# xen_teensy_controls_template.net
KiCad netlist of a schematic drawn in EAGLE
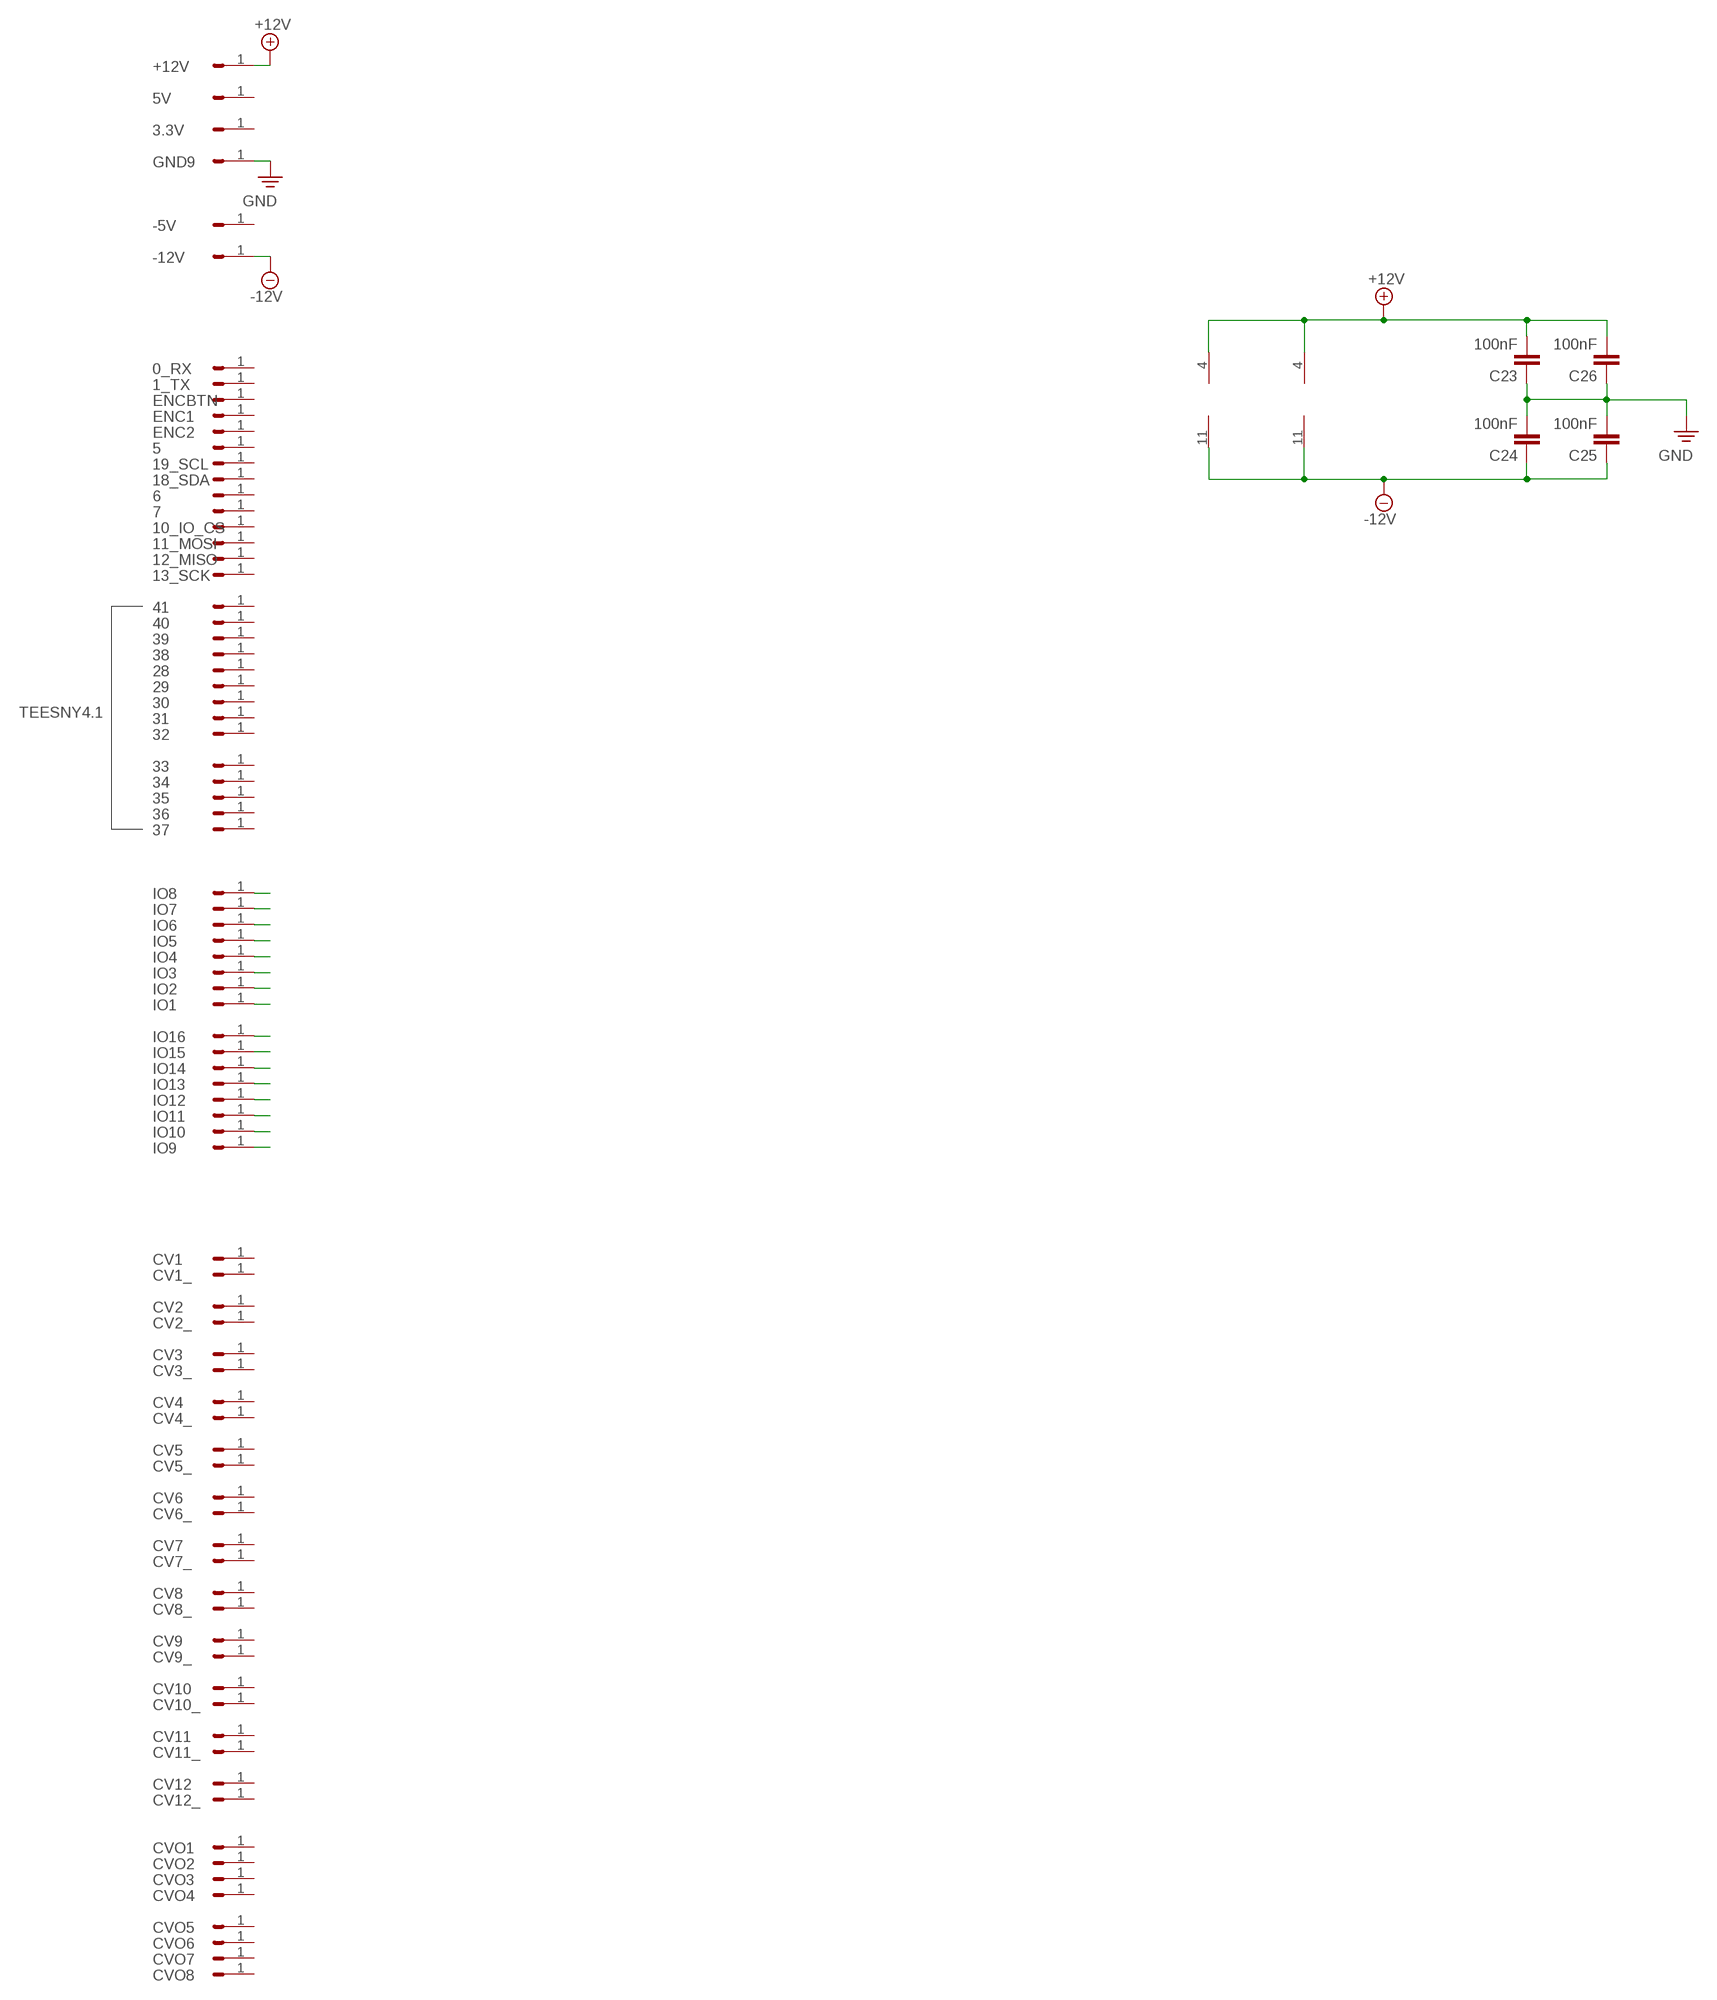
[diagram p0: schematic, sheet 1]

(export (version "E")
  (design (tool "Eeschema 10.0.6"))
  (components
    (comp (ref "+12V")
      (value "HEADER/MALE/01")
      (footprint "eagle-import:HEADER_MALE_01")
      (fields (field (name "SPICEPREFIX") "X"))
      (libsource (lib "eagle-import") (part "HEADER/MALE/01"))
    )
    (comp (ref "-5V")
      (value "HEADER/MALE/01")
      (footprint "eagle-import:HEADER_MALE_01")
      (fields (field (name "SPICEPREFIX") "X"))
      (libsource (lib "eagle-import") (part "HEADER/MALE/01"))
    )
    (comp (ref "-12V")
      (value "HEADER/MALE/01")
      (footprint "eagle-import:HEADER_MALE_01")
      (fields (field (name "SPICEPREFIX") "X"))
      (libsource (lib "eagle-import") (part "HEADER/MALE/01"))
    )
    (comp (ref "0_RX")
      (value "HEADER/MALE/01")
      (footprint "eagle-import:HEADER_MALE_01")
      (fields (field (name "SPICEPREFIX") "X"))
      (libsource (lib "eagle-import") (part "HEADER/MALE/01"))
    )
    (comp (ref "1_TX")
      (value "HEADER/MALE/01")
      (footprint "eagle-import:HEADER_MALE_01")
      (fields (field (name "SPICEPREFIX") "X"))
      (libsource (lib "eagle-import") (part "HEADER/MALE/01"))
    )
    (comp (ref "3.3V")
      (value "HEADER/MALE/01")
      (footprint "eagle-import:HEADER_MALE_01")
      (fields (field (name "SPICEPREFIX") "X"))
      (libsource (lib "eagle-import") (part "HEADER/MALE/01"))
    )
    (comp (ref "5")
      (value "HEADER/MALE/01")
      (footprint "eagle-import:HEADER_MALE_01")
      (fields (field (name "SPICEPREFIX") "X"))
      (libsource (lib "eagle-import") (part "HEADER/MALE/01"))
    )
    (comp (ref "5V")
      (value "HEADER/MALE/01")
      (footprint "eagle-import:HEADER_MALE_01")
      (fields (field (name "SPICEPREFIX") "X"))
      (libsource (lib "eagle-import") (part "HEADER/MALE/01"))
    )
    (comp (ref "6")
      (value "HEADER/MALE/01")
      (footprint "eagle-import:HEADER_MALE_01")
      (fields (field (name "SPICEPREFIX") "X"))
      (libsource (lib "eagle-import") (part "HEADER/MALE/01"))
    )
    (comp (ref "7")
      (value "HEADER/MALE/01")
      (footprint "eagle-import:HEADER_MALE_01")
      (fields (field (name "SPICEPREFIX") "X"))
      (libsource (lib "eagle-import") (part "HEADER/MALE/01"))
    )
    (comp (ref "10_IO_CS")
      (value "HEADER/MALE/01")
      (footprint "eagle-import:HEADER_MALE_01")
      (fields (field (name "SPICEPREFIX") "X"))
      (libsource (lib "eagle-import") (part "HEADER/MALE/01"))
    )
    (comp (ref "11_MOSI")
      (value "HEADER/MALE/01")
      (footprint "eagle-import:HEADER_MALE_01")
      (fields (field (name "SPICEPREFIX") "X"))
      (libsource (lib "eagle-import") (part "HEADER/MALE/01"))
    )
    (comp (ref "12_MISO")
      (value "HEADER/MALE/01")
      (footprint "eagle-import:HEADER_MALE_01")
      (fields (field (name "SPICEPREFIX") "X"))
      (libsource (lib "eagle-import") (part "HEADER/MALE/01"))
    )
    (comp (ref "13_SCK")
      (value "HEADER/MALE/01")
      (footprint "eagle-import:HEADER_MALE_01")
      (fields (field (name "SPICEPREFIX") "X"))
      (libsource (lib "eagle-import") (part "HEADER/MALE/01"))
    )
    (comp (ref "18_SDA")
      (value "HEADER/MALE/01")
      (footprint "eagle-import:HEADER_MALE_01")
      (fields (field (name "SPICEPREFIX") "X"))
      (libsource (lib "eagle-import") (part "HEADER/MALE/01"))
    )
    (comp (ref "19_SCL")
      (value "HEADER/MALE/01")
      (footprint "eagle-import:HEADER_MALE_01")
      (fields (field (name "SPICEPREFIX") "X"))
      (libsource (lib "eagle-import") (part "HEADER/MALE/01"))
    )
    (comp (ref "28")
      (value "HEADER/MALE/01")
      (footprint "eagle-import:HEADER_MALE_01")
      (fields (field (name "SPICEPREFIX") "X"))
      (libsource (lib "eagle-import") (part "HEADER/MALE/01"))
    )
    (comp (ref "29")
      (value "HEADER/MALE/01")
      (footprint "eagle-import:HEADER_MALE_01")
      (fields (field (name "SPICEPREFIX") "X"))
      (libsource (lib "eagle-import") (part "HEADER/MALE/01"))
    )
    (comp (ref "30")
      (value "HEADER/MALE/01")
      (footprint "eagle-import:HEADER_MALE_01")
      (fields (field (name "SPICEPREFIX") "X"))
      (libsource (lib "eagle-import") (part "HEADER/MALE/01"))
    )
    (comp (ref "31")
      (value "HEADER/MALE/01")
      (footprint "eagle-import:HEADER_MALE_01")
      (fields (field (name "SPICEPREFIX") "X"))
      (libsource (lib "eagle-import") (part "HEADER/MALE/01"))
    )
    (comp (ref "32")
      (value "HEADER/MALE/01")
      (footprint "eagle-import:HEADER_MALE_01")
      (fields (field (name "SPICEPREFIX") "X"))
      (libsource (lib "eagle-import") (part "HEADER/MALE/01"))
    )
    (comp (ref "33")
      (value "HEADER/MALE/01")
      (footprint "eagle-import:HEADER_MALE_01")
      (fields (field (name "SPICEPREFIX") "X"))
      (libsource (lib "eagle-import") (part "HEADER/MALE/01"))
    )
    (comp (ref "34")
      (value "HEADER/MALE/01")
      (footprint "eagle-import:HEADER_MALE_01")
      (fields (field (name "SPICEPREFIX") "X"))
      (libsource (lib "eagle-import") (part "HEADER/MALE/01"))
    )
    (comp (ref "35")
      (value "HEADER/MALE/01")
      (footprint "eagle-import:HEADER_MALE_01")
      (fields (field (name "SPICEPREFIX") "X"))
      (libsource (lib "eagle-import") (part "HEADER/MALE/01"))
    )
    (comp (ref "36")
      (value "HEADER/MALE/01")
      (footprint "eagle-import:HEADER_MALE_01")
      (fields (field (name "SPICEPREFIX") "X"))
      (libsource (lib "eagle-import") (part "HEADER/MALE/01"))
    )
    (comp (ref "37")
      (value "HEADER/MALE/01")
      (footprint "eagle-import:HEADER_MALE_01")
      (fields (field (name "SPICEPREFIX") "X"))
      (libsource (lib "eagle-import") (part "HEADER/MALE/01"))
    )
    (comp (ref "38")
      (value "HEADER/MALE/01")
      (footprint "eagle-import:HEADER_MALE_01")
      (fields (field (name "SPICEPREFIX") "X"))
      (libsource (lib "eagle-import") (part "HEADER/MALE/01"))
    )
    (comp (ref "39")
      (value "HEADER/MALE/01")
      (footprint "eagle-import:HEADER_MALE_01")
      (fields (field (name "SPICEPREFIX") "X"))
      (libsource (lib "eagle-import") (part "HEADER/MALE/01"))
    )
    (comp (ref "40")
      (value "HEADER/MALE/01")
      (footprint "eagle-import:HEADER_MALE_01")
      (fields (field (name "SPICEPREFIX") "X"))
      (libsource (lib "eagle-import") (part "HEADER/MALE/01"))
    )
    (comp (ref "41")
      (value "HEADER/MALE/01")
      (footprint "eagle-import:HEADER_MALE_01")
      (fields (field (name "SPICEPREFIX") "X"))
      (libsource (lib "eagle-import") (part "HEADER/MALE/01"))
    )
    (comp (ref "C23")
      (value "100nF")
      (footprint "eagle-import:C0603")
      (libsource (lib "eagle-import") (part "CAPACITORC0603"))
    )
    (comp (ref "C24")
      (value "100nF")
      (footprint "eagle-import:C0603")
      (libsource (lib "eagle-import") (part "CAPACITORC0603"))
    )
    (comp (ref "C25")
      (value "100nF")
      (footprint "eagle-import:C0603")
      (libsource (lib "eagle-import") (part "CAPACITORC0603"))
    )
    (comp (ref "C26")
      (value "100nF")
      (footprint "eagle-import:C0603")
      (libsource (lib "eagle-import") (part "CAPACITORC0603"))
    )
    (comp (ref "CV1")
      (value "HEADER/MALE/01")
      (footprint "eagle-import:HEADER_MALE_01")
      (fields (field (name "SPICEPREFIX") "X"))
      (libsource (lib "eagle-import") (part "HEADER/MALE/01"))
    )
    (comp (ref "CV1_")
      (value "HEADER/MALE/01")
      (footprint "eagle-import:HEADER_MALE_01")
      (fields (field (name "SPICEPREFIX") "X"))
      (libsource (lib "eagle-import") (part "HEADER/MALE/01"))
    )
    (comp (ref "CV2")
      (value "HEADER/MALE/01")
      (footprint "eagle-import:HEADER_MALE_01")
      (fields (field (name "SPICEPREFIX") "X"))
      (libsource (lib "eagle-import") (part "HEADER/MALE/01"))
    )
    (comp (ref "CV2_")
      (value "HEADER/MALE/01")
      (footprint "eagle-import:HEADER_MALE_01")
      (fields (field (name "SPICEPREFIX") "X"))
      (libsource (lib "eagle-import") (part "HEADER/MALE/01"))
    )
    (comp (ref "CV3")
      (value "HEADER/MALE/01")
      (footprint "eagle-import:HEADER_MALE_01")
      (fields (field (name "SPICEPREFIX") "X"))
      (libsource (lib "eagle-import") (part "HEADER/MALE/01"))
    )
    (comp (ref "CV3_")
      (value "HEADER/MALE/01")
      (footprint "eagle-import:HEADER_MALE_01")
      (fields (field (name "SPICEPREFIX") "X"))
      (libsource (lib "eagle-import") (part "HEADER/MALE/01"))
    )
    (comp (ref "CV4")
      (value "HEADER/MALE/01")
      (footprint "eagle-import:HEADER_MALE_01")
      (fields (field (name "SPICEPREFIX") "X"))
      (libsource (lib "eagle-import") (part "HEADER/MALE/01"))
    )
    (comp (ref "CV4_")
      (value "HEADER/MALE/01")
      (footprint "eagle-import:HEADER_MALE_01")
      (fields (field (name "SPICEPREFIX") "X"))
      (libsource (lib "eagle-import") (part "HEADER/MALE/01"))
    )
    (comp (ref "CV5")
      (value "HEADER/MALE/01")
      (footprint "eagle-import:HEADER_MALE_01")
      (fields (field (name "SPICEPREFIX") "X"))
      (libsource (lib "eagle-import") (part "HEADER/MALE/01"))
    )
    (comp (ref "CV5_")
      (value "HEADER/MALE/01")
      (footprint "eagle-import:HEADER_MALE_01")
      (fields (field (name "SPICEPREFIX") "X"))
      (libsource (lib "eagle-import") (part "HEADER/MALE/01"))
    )
    (comp (ref "CV6")
      (value "HEADER/MALE/01")
      (footprint "eagle-import:HEADER_MALE_01")
      (fields (field (name "SPICEPREFIX") "X"))
      (libsource (lib "eagle-import") (part "HEADER/MALE/01"))
    )
    (comp (ref "CV6_")
      (value "HEADER/MALE/01")
      (footprint "eagle-import:HEADER_MALE_01")
      (fields (field (name "SPICEPREFIX") "X"))
      (libsource (lib "eagle-import") (part "HEADER/MALE/01"))
    )
    (comp (ref "CV7")
      (value "HEADER/MALE/01")
      (footprint "eagle-import:HEADER_MALE_01")
      (fields (field (name "SPICEPREFIX") "X"))
      (libsource (lib "eagle-import") (part "HEADER/MALE/01"))
    )
    (comp (ref "CV7_")
      (value "HEADER/MALE/01")
      (footprint "eagle-import:HEADER_MALE_01")
      (fields (field (name "SPICEPREFIX") "X"))
      (libsource (lib "eagle-import") (part "HEADER/MALE/01"))
    )
    (comp (ref "CV8")
      (value "HEADER/MALE/01")
      (footprint "eagle-import:HEADER_MALE_01")
      (fields (field (name "SPICEPREFIX") "X"))
      (libsource (lib "eagle-import") (part "HEADER/MALE/01"))
    )
    (comp (ref "CV8_")
      (value "HEADER/MALE/01")
      (footprint "eagle-import:HEADER_MALE_01")
      (fields (field (name "SPICEPREFIX") "X"))
      (libsource (lib "eagle-import") (part "HEADER/MALE/01"))
    )
    (comp (ref "CV9")
      (value "HEADER/MALE/01")
      (footprint "eagle-import:HEADER_MALE_01")
      (fields (field (name "SPICEPREFIX") "X"))
      (libsource (lib "eagle-import") (part "HEADER/MALE/01"))
    )
    (comp (ref "CV9_")
      (value "HEADER/MALE/01")
      (footprint "eagle-import:HEADER_MALE_01")
      (fields (field (name "SPICEPREFIX") "X"))
      (libsource (lib "eagle-import") (part "HEADER/MALE/01"))
    )
    (comp (ref "CV10")
      (value "HEADER/MALE/01")
      (footprint "eagle-import:HEADER_MALE_01")
      (fields (field (name "SPICEPREFIX") "X"))
      (libsource (lib "eagle-import") (part "HEADER/MALE/01"))
    )
    (comp (ref "CV10_")
      (value "HEADER/MALE/01")
      (footprint "eagle-import:HEADER_MALE_01")
      (fields (field (name "SPICEPREFIX") "X"))
      (libsource (lib "eagle-import") (part "HEADER/MALE/01"))
    )
    (comp (ref "CV11")
      (value "HEADER/MALE/01")
      (footprint "eagle-import:HEADER_MALE_01")
      (fields (field (name "SPICEPREFIX") "X"))
      (libsource (lib "eagle-import") (part "HEADER/MALE/01"))
    )
    (comp (ref "CV11_")
      (value "HEADER/MALE/01")
      (footprint "eagle-import:HEADER_MALE_01")
      (fields (field (name "SPICEPREFIX") "X"))
      (libsource (lib "eagle-import") (part "HEADER/MALE/01"))
    )
    (comp (ref "CV12")
      (value "HEADER/MALE/01")
      (footprint "eagle-import:HEADER_MALE_01")
      (fields (field (name "SPICEPREFIX") "X"))
      (libsource (lib "eagle-import") (part "HEADER/MALE/01"))
    )
    (comp (ref "CV12_")
      (value "HEADER/MALE/01")
      (footprint "eagle-import:HEADER_MALE_01")
      (fields (field (name "SPICEPREFIX") "X"))
      (libsource (lib "eagle-import") (part "HEADER/MALE/01"))
    )
    (comp (ref "CVO1")
      (value "HEADER/MALE/01")
      (footprint "eagle-import:HEADER_MALE_01")
      (fields (field (name "SPICEPREFIX") "X"))
      (libsource (lib "eagle-import") (part "HEADER/MALE/01"))
    )
    (comp (ref "CVO2")
      (value "HEADER/MALE/01")
      (footprint "eagle-import:HEADER_MALE_01")
      (fields (field (name "SPICEPREFIX") "X"))
      (libsource (lib "eagle-import") (part "HEADER/MALE/01"))
    )
    (comp (ref "CVO3")
      (value "HEADER/MALE/01")
      (footprint "eagle-import:HEADER_MALE_01")
      (fields (field (name "SPICEPREFIX") "X"))
      (libsource (lib "eagle-import") (part "HEADER/MALE/01"))
    )
    (comp (ref "CVO4")
      (value "HEADER/MALE/01")
      (footprint "eagle-import:HEADER_MALE_01")
      (fields (field (name "SPICEPREFIX") "X"))
      (libsource (lib "eagle-import") (part "HEADER/MALE/01"))
    )
    (comp (ref "CVO5")
      (value "HEADER/MALE/01")
      (footprint "eagle-import:HEADER_MALE_01")
      (fields (field (name "SPICEPREFIX") "X"))
      (libsource (lib "eagle-import") (part "HEADER/MALE/01"))
    )
    (comp (ref "CVO6")
      (value "HEADER/MALE/01")
      (footprint "eagle-import:HEADER_MALE_01")
      (fields (field (name "SPICEPREFIX") "X"))
      (libsource (lib "eagle-import") (part "HEADER/MALE/01"))
    )
    (comp (ref "CVO7")
      (value "HEADER/MALE/01")
      (footprint "eagle-import:HEADER_MALE_01")
      (fields (field (name "SPICEPREFIX") "X"))
      (libsource (lib "eagle-import") (part "HEADER/MALE/01"))
    )
    (comp (ref "CVO8")
      (value "HEADER/MALE/01")
      (footprint "eagle-import:HEADER_MALE_01")
      (fields (field (name "SPICEPREFIX") "X"))
      (libsource (lib "eagle-import") (part "HEADER/MALE/01"))
    )
    (comp (ref "ENC1")
      (value "HEADER/MALE/01")
      (footprint "eagle-import:HEADER_MALE_01")
      (fields (field (name "SPICEPREFIX") "X"))
      (libsource (lib "eagle-import") (part "HEADER/MALE/01"))
    )
    (comp (ref "ENC2")
      (value "HEADER/MALE/01")
      (footprint "eagle-import:HEADER_MALE_01")
      (fields (field (name "SPICEPREFIX") "X"))
      (libsource (lib "eagle-import") (part "HEADER/MALE/01"))
    )
    (comp (ref "ENCBTN")
      (value "HEADER/MALE/01")
      (footprint "eagle-import:HEADER_MALE_01")
      (fields (field (name "SPICEPREFIX") "X"))
      (libsource (lib "eagle-import") (part "HEADER/MALE/01"))
    )
    (comp (ref "GND9")
      (value "HEADER/MALE/01")
      (footprint "eagle-import:HEADER_MALE_01")
      (fields (field (name "SPICEPREFIX") "X"))
      (libsource (lib "eagle-import") (part "HEADER/MALE/01"))
    )
    (comp (ref "IC1")
      (value "TL074D")
      (footprint "eagle-import:SO14")
      (libsource (lib "eagle-import") (part "TL074D"))
    )
    (comp (ref "IC5")
      (value "TL074D")
      (footprint "eagle-import:SO14")
      (libsource (lib "eagle-import") (part "TL074D"))
    )
    (comp (ref "IO1")
      (value "HEADER/MALE/01")
      (footprint "eagle-import:HEADER_MALE_01")
      (fields (field (name "SPICEPREFIX") "X"))
      (libsource (lib "eagle-import") (part "HEADER/MALE/01"))
    )
    (comp (ref "IO2")
      (value "HEADER/MALE/01")
      (footprint "eagle-import:HEADER_MALE_01")
      (fields (field (name "SPICEPREFIX") "X"))
      (libsource (lib "eagle-import") (part "HEADER/MALE/01"))
    )
    (comp (ref "IO3")
      (value "HEADER/MALE/01")
      (footprint "eagle-import:HEADER_MALE_01")
      (fields (field (name "SPICEPREFIX") "X"))
      (libsource (lib "eagle-import") (part "HEADER/MALE/01"))
    )
    (comp (ref "IO4")
      (value "HEADER/MALE/01")
      (footprint "eagle-import:HEADER_MALE_01")
      (fields (field (name "SPICEPREFIX") "X"))
      (libsource (lib "eagle-import") (part "HEADER/MALE/01"))
    )
    (comp (ref "IO5")
      (value "HEADER/MALE/01")
      (footprint "eagle-import:HEADER_MALE_01")
      (fields (field (name "SPICEPREFIX") "X"))
      (libsource (lib "eagle-import") (part "HEADER/MALE/01"))
    )
    (comp (ref "IO6")
      (value "HEADER/MALE/01")
      (footprint "eagle-import:HEADER_MALE_01")
      (fields (field (name "SPICEPREFIX") "X"))
      (libsource (lib "eagle-import") (part "HEADER/MALE/01"))
    )
    (comp (ref "IO7")
      (value "HEADER/MALE/01")
      (footprint "eagle-import:HEADER_MALE_01")
      (fields (field (name "SPICEPREFIX") "X"))
      (libsource (lib "eagle-import") (part "HEADER/MALE/01"))
    )
    (comp (ref "IO8")
      (value "HEADER/MALE/01")
      (footprint "eagle-import:HEADER_MALE_01")
      (fields (field (name "SPICEPREFIX") "X"))
      (libsource (lib "eagle-import") (part "HEADER/MALE/01"))
    )
    (comp (ref "IO9")
      (value "HEADER/MALE/01")
      (footprint "eagle-import:HEADER_MALE_01")
      (fields (field (name "SPICEPREFIX") "X"))
      (libsource (lib "eagle-import") (part "HEADER/MALE/01"))
    )
    (comp (ref "IO10")
      (value "HEADER/MALE/01")
      (footprint "eagle-import:HEADER_MALE_01")
      (fields (field (name "SPICEPREFIX") "X"))
      (libsource (lib "eagle-import") (part "HEADER/MALE/01"))
    )
    (comp (ref "IO11")
      (value "HEADER/MALE/01")
      (footprint "eagle-import:HEADER_MALE_01")
      (fields (field (name "SPICEPREFIX") "X"))
      (libsource (lib "eagle-import") (part "HEADER/MALE/01"))
    )
    (comp (ref "IO12")
      (value "HEADER/MALE/01")
      (footprint "eagle-import:HEADER_MALE_01")
      (fields (field (name "SPICEPREFIX") "X"))
      (libsource (lib "eagle-import") (part "HEADER/MALE/01"))
    )
    (comp (ref "IO13")
      (value "HEADER/MALE/01")
      (footprint "eagle-import:HEADER_MALE_01")
      (fields (field (name "SPICEPREFIX") "X"))
      (libsource (lib "eagle-import") (part "HEADER/MALE/01"))
    )
    (comp (ref "IO14")
      (value "HEADER/MALE/01")
      (footprint "eagle-import:HEADER_MALE_01")
      (fields (field (name "SPICEPREFIX") "X"))
      (libsource (lib "eagle-import") (part "HEADER/MALE/01"))
    )
    (comp (ref "IO15")
      (value "HEADER/MALE/01")
      (footprint "eagle-import:HEADER_MALE_01")
      (fields (field (name "SPICEPREFIX") "X"))
      (libsource (lib "eagle-import") (part "HEADER/MALE/01"))
    )
    (comp (ref "IO16")
      (value "HEADER/MALE/01")
      (footprint "eagle-import:HEADER_MALE_01")
      (fields (field (name "SPICEPREFIX") "X"))
      (libsource (lib "eagle-import") (part "HEADER/MALE/01"))
    )
  )
  (nets
    (net (code "1") (name "+12V") (class "Default")
      (node (ref "+12V") (pin "1") (pinfunction "3_1") (pintype "passive"))
      (node (ref "C23") (pin "2") (pinfunction "2_2") (pintype "passive"))
      (node (ref "C26") (pin "2") (pinfunction "2_2") (pintype "passive"))
      (node (ref "IC1") (pin "4") (pinfunction "V+_4") (pintype "power_in"))
      (node (ref "IC5") (pin "4") (pinfunction "V+_4") (pintype "power_in"))
    )
    (net (code "2") (name "-12V") (class "Default")
      (node (ref "-12V") (pin "1") (pinfunction "3_1") (pintype "passive"))
      (node (ref "C24") (pin "1") (pinfunction "1_1") (pintype "passive"))
      (node (ref "C25") (pin "1") (pinfunction "1_1") (pintype "passive"))
      (node (ref "IC1") (pin "11") (pinfunction "V-_11") (pintype "power_in"))
      (node (ref "IC5") (pin "11") (pinfunction "V-_11") (pintype "power_in"))
    )
    (net (code "3") (name "GND") (class "Default")
      (node (ref "C23") (pin "1") (pinfunction "1_1") (pintype "passive"))
      (node (ref "C24") (pin "2") (pinfunction "2_2") (pintype "passive"))
      (node (ref "C25") (pin "2") (pinfunction "2_2") (pintype "passive"))
      (node (ref "C26") (pin "1") (pinfunction "1_1") (pintype "passive"))
      (node (ref "GND9") (pin "1") (pinfunction "3_1") (pintype "passive"))
    )
    (net (code "4") (name "unconnected-(-5V-3-Pad1)") (class "Default")
      (node (ref "-5V") (pin "1") (pinfunction "3_1") (pintype "passive"))
    )
    (net (code "5") (name "unconnected-(0_RX-3-Pad1)") (class "Default")
      (node (ref "0_RX") (pin "1") (pinfunction "3_1") (pintype "passive"))
    )
    (net (code "6") (name "unconnected-(1_TX-3-Pad1)") (class "Default")
      (node (ref "1_TX") (pin "1") (pinfunction "3_1") (pintype "passive"))
    )
    (net (code "7") (name "unconnected-(3.3V-3-Pad1)") (class "Default")
      (node (ref "3.3V") (pin "1") (pinfunction "3_1") (pintype "passive"))
    )
    (net (code "8") (name "unconnected-(5-3-Pad1)") (class "Default")
      (node (ref "5") (pin "1") (pinfunction "3_1") (pintype "passive"))
    )
    (net (code "9") (name "unconnected-(5V-3-Pad1)") (class "Default")
      (node (ref "5V") (pin "1") (pinfunction "3_1") (pintype "passive"))
    )
    (net (code "10") (name "unconnected-(6-3-Pad1)") (class "Default")
      (node (ref "6") (pin "1") (pinfunction "3_1") (pintype "passive"))
    )
    (net (code "11") (name "unconnected-(7-3-Pad1)") (class "Default")
      (node (ref "7") (pin "1") (pinfunction "3_1") (pintype "passive"))
    )
    (net (code "12") (name "unconnected-(10_IO_CS-3-Pad1)") (class "Default")
      (node (ref "10_IO_CS") (pin "1") (pinfunction "3_1") (pintype "passive"))
    )
    (net (code "13") (name "unconnected-(11_MOSI-3-Pad1)") (class "Default")
      (node (ref "11_MOSI") (pin "1") (pinfunction "3_1") (pintype "passive"))
    )
    (net (code "14") (name "unconnected-(12_MISO-3-Pad1)") (class "Default")
      (node (ref "12_MISO") (pin "1") (pinfunction "3_1") (pintype "passive"))
    )
    (net (code "15") (name "unconnected-(13_SCK-3-Pad1)") (class "Default")
      (node (ref "13_SCK") (pin "1") (pinfunction "3_1") (pintype "passive"))
    )
    (net (code "16") (name "unconnected-(18_SDA-3-Pad1)") (class "Default")
      (node (ref "18_SDA") (pin "1") (pinfunction "3_1") (pintype "passive"))
    )
    (net (code "17") (name "unconnected-(19_SCL-3-Pad1)") (class "Default")
      (node (ref "19_SCL") (pin "1") (pinfunction "3_1") (pintype "passive"))
    )
    (net (code "18") (name "unconnected-(28-3-Pad1)") (class "Default")
      (node (ref "28") (pin "1") (pinfunction "3_1") (pintype "passive"))
    )
    (net (code "19") (name "unconnected-(29-3-Pad1)") (class "Default")
      (node (ref "29") (pin "1") (pinfunction "3_1") (pintype "passive"))
    )
    (net (code "20") (name "unconnected-(30-3-Pad1)") (class "Default")
      (node (ref "30") (pin "1") (pinfunction "3_1") (pintype "passive"))
    )
    (net (code "21") (name "unconnected-(31-3-Pad1)") (class "Default")
      (node (ref "31") (pin "1") (pinfunction "3_1") (pintype "passive"))
    )
    (net (code "22") (name "unconnected-(32-3-Pad1)") (class "Default")
      (node (ref "32") (pin "1") (pinfunction "3_1") (pintype "passive"))
    )
    (net (code "23") (name "unconnected-(33-3-Pad1)") (class "Default")
      (node (ref "33") (pin "1") (pinfunction "3_1") (pintype "passive"))
    )
    (net (code "24") (name "unconnected-(34-3-Pad1)") (class "Default")
      (node (ref "34") (pin "1") (pinfunction "3_1") (pintype "passive"))
    )
    (net (code "25") (name "unconnected-(35-3-Pad1)") (class "Default")
      (node (ref "35") (pin "1") (pinfunction "3_1") (pintype "passive"))
    )
    (net (code "26") (name "unconnected-(36-3-Pad1)") (class "Default")
      (node (ref "36") (pin "1") (pinfunction "3_1") (pintype "passive"))
    )
    (net (code "27") (name "unconnected-(37-3-Pad1)") (class "Default")
      (node (ref "37") (pin "1") (pinfunction "3_1") (pintype "passive"))
    )
    (net (code "28") (name "unconnected-(38-3-Pad1)") (class "Default")
      (node (ref "38") (pin "1") (pinfunction "3_1") (pintype "passive"))
    )
    (net (code "29") (name "unconnected-(39-3-Pad1)") (class "Default")
      (node (ref "39") (pin "1") (pinfunction "3_1") (pintype "passive"))
    )
    (net (code "30") (name "unconnected-(40-3-Pad1)") (class "Default")
      (node (ref "40") (pin "1") (pinfunction "3_1") (pintype "passive"))
    )
    (net (code "31") (name "unconnected-(41-3-Pad1)") (class "Default")
      (node (ref "41") (pin "1") (pinfunction "3_1") (pintype "passive"))
    )
    (net (code "32") (name "unconnected-(CV1-3-Pad1)") (class "Default")
      (node (ref "CV1") (pin "1") (pinfunction "3_1") (pintype "passive"))
    )
    (net (code "33") (name "unconnected-(CV1_-3-Pad1)") (class "Default")
      (node (ref "CV1_") (pin "1") (pinfunction "3_1") (pintype "passive"))
    )
    (net (code "34") (name "unconnected-(CV2-3-Pad1)") (class "Default")
      (node (ref "CV2") (pin "1") (pinfunction "3_1") (pintype "passive"))
    )
    (net (code "35") (name "unconnected-(CV2_-3-Pad1)") (class "Default")
      (node (ref "CV2_") (pin "1") (pinfunction "3_1") (pintype "passive"))
    )
    (net (code "36") (name "unconnected-(CV3-3-Pad1)") (class "Default")
      (node (ref "CV3") (pin "1") (pinfunction "3_1") (pintype "passive"))
    )
    (net (code "37") (name "unconnected-(CV3_-3-Pad1)") (class "Default")
      (node (ref "CV3_") (pin "1") (pinfunction "3_1") (pintype "passive"))
    )
    (net (code "38") (name "unconnected-(CV4-3-Pad1)") (class "Default")
      (node (ref "CV4") (pin "1") (pinfunction "3_1") (pintype "passive"))
    )
    (net (code "39") (name "unconnected-(CV4_-3-Pad1)") (class "Default")
      (node (ref "CV4_") (pin "1") (pinfunction "3_1") (pintype "passive"))
    )
    (net (code "40") (name "unconnected-(CV5-3-Pad1)") (class "Default")
      (node (ref "CV5") (pin "1") (pinfunction "3_1") (pintype "passive"))
    )
    (net (code "41") (name "unconnected-(CV5_-3-Pad1)") (class "Default")
      (node (ref "CV5_") (pin "1") (pinfunction "3_1") (pintype "passive"))
    )
    (net (code "42") (name "unconnected-(CV6-3-Pad1)") (class "Default")
      (node (ref "CV6") (pin "1") (pinfunction "3_1") (pintype "passive"))
    )
    (net (code "43") (name "unconnected-(CV6_-3-Pad1)") (class "Default")
      (node (ref "CV6_") (pin "1") (pinfunction "3_1") (pintype "passive"))
    )
    (net (code "44") (name "unconnected-(CV7-3-Pad1)") (class "Default")
      (node (ref "CV7") (pin "1") (pinfunction "3_1") (pintype "passive"))
    )
    (net (code "45") (name "unconnected-(CV7_-3-Pad1)") (class "Default")
      (node (ref "CV7_") (pin "1") (pinfunction "3_1") (pintype "passive"))
    )
    (net (code "46") (name "unconnected-(CV8-3-Pad1)") (class "Default")
      (node (ref "CV8") (pin "1") (pinfunction "3_1") (pintype "passive"))
    )
    (net (code "47") (name "unconnected-(CV8_-3-Pad1)") (class "Default")
      (node (ref "CV8_") (pin "1") (pinfunction "3_1") (pintype "passive"))
    )
    (net (code "48") (name "unconnected-(CV9-3-Pad1)") (class "Default")
      (node (ref "CV9") (pin "1") (pinfunction "3_1") (pintype "passive"))
    )
    (net (code "49") (name "unconnected-(CV9_-3-Pad1)") (class "Default")
      (node (ref "CV9_") (pin "1") (pinfunction "3_1") (pintype "passive"))
    )
    (net (code "50") (name "unconnected-(CV10-3-Pad1)") (class "Default")
      (node (ref "CV10") (pin "1") (pinfunction "3_1") (pintype "passive"))
    )
    (net (code "51") (name "unconnected-(CV10_-3-Pad1)") (class "Default")
      (node (ref "CV10_") (pin "1") (pinfunction "3_1") (pintype "passive"))
    )
    (net (code "52") (name "unconnected-(CV11-3-Pad1)") (class "Default")
      (node (ref "CV11") (pin "1") (pinfunction "3_1") (pintype "passive"))
    )
    (net (code "53") (name "unconnected-(CV11_-3-Pad1)") (class "Default")
      (node (ref "CV11_") (pin "1") (pinfunction "3_1") (pintype "passive"))
    )
    (net (code "54") (name "unconnected-(CV12-3-Pad1)") (class "Default")
      (node (ref "CV12") (pin "1") (pinfunction "3_1") (pintype "passive"))
    )
    (net (code "55") (name "unconnected-(CV12_-3-Pad1)") (class "Default")
      (node (ref "CV12_") (pin "1") (pinfunction "3_1") (pintype "passive"))
    )
    (net (code "56") (name "unconnected-(CVO1-3-Pad1)") (class "Default")
      (node (ref "CVO1") (pin "1") (pinfunction "3_1") (pintype "passive"))
    )
    (net (code "57") (name "unconnected-(CVO2-3-Pad1)") (class "Default")
      (node (ref "CVO2") (pin "1") (pinfunction "3_1") (pintype "passive"))
    )
    (net (code "58") (name "unconnected-(CVO3-3-Pad1)") (class "Default")
      (node (ref "CVO3") (pin "1") (pinfunction "3_1") (pintype "passive"))
    )
    (net (code "59") (name "unconnected-(CVO4-3-Pad1)") (class "Default")
      (node (ref "CVO4") (pin "1") (pinfunction "3_1") (pintype "passive"))
    )
    (net (code "60") (name "unconnected-(CVO5-3-Pad1)") (class "Default")
      (node (ref "CVO5") (pin "1") (pinfunction "3_1") (pintype "passive"))
    )
    (net (code "61") (name "unconnected-(CVO6-3-Pad1)") (class "Default")
      (node (ref "CVO6") (pin "1") (pinfunction "3_1") (pintype "passive"))
    )
    (net (code "62") (name "unconnected-(CVO7-3-Pad1)") (class "Default")
      (node (ref "CVO7") (pin "1") (pinfunction "3_1") (pintype "passive"))
    )
    (net (code "63") (name "unconnected-(CVO8-3-Pad1)") (class "Default")
      (node (ref "CVO8") (pin "1") (pinfunction "3_1") (pintype "passive"))
    )
    (net (code "64") (name "unconnected-(ENC1-3-Pad1)") (class "Default")
      (node (ref "ENC1") (pin "1") (pinfunction "3_1") (pintype "passive"))
    )
    (net (code "65") (name "unconnected-(ENC2-3-Pad1)") (class "Default")
      (node (ref "ENC2") (pin "1") (pinfunction "3_1") (pintype "passive"))
    )
    (net (code "66") (name "unconnected-(ENCBTN-3-Pad1)") (class "Default")
      (node (ref "ENCBTN") (pin "1") (pinfunction "3_1") (pintype "passive"))
    )
    (net (code "67") (name "unconnected-(IO1-3-Pad1)") (class "Default")
      (node (ref "IO1") (pin "1") (pinfunction "3_1") (pintype "passive"))
    )
    (net (code "68") (name "unconnected-(IO2-3-Pad1)") (class "Default")
      (node (ref "IO2") (pin "1") (pinfunction "3_1") (pintype "passive"))
    )
    (net (code "69") (name "unconnected-(IO3-3-Pad1)") (class "Default")
      (node (ref "IO3") (pin "1") (pinfunction "3_1") (pintype "passive"))
    )
    (net (code "70") (name "unconnected-(IO4-3-Pad1)") (class "Default")
      (node (ref "IO4") (pin "1") (pinfunction "3_1") (pintype "passive"))
    )
    (net (code "71") (name "unconnected-(IO5-3-Pad1)") (class "Default")
      (node (ref "IO5") (pin "1") (pinfunction "3_1") (pintype "passive"))
    )
    (net (code "72") (name "unconnected-(IO6-3-Pad1)") (class "Default")
      (node (ref "IO6") (pin "1") (pinfunction "3_1") (pintype "passive"))
    )
    (net (code "73") (name "unconnected-(IO7-3-Pad1)") (class "Default")
      (node (ref "IO7") (pin "1") (pinfunction "3_1") (pintype "passive"))
    )
    (net (code "74") (name "unconnected-(IO8-3-Pad1)") (class "Default")
      (node (ref "IO8") (pin "1") (pinfunction "3_1") (pintype "passive"))
    )
    (net (code "75") (name "unconnected-(IO9-3-Pad1)") (class "Default")
      (node (ref "IO9") (pin "1") (pinfunction "3_1") (pintype "passive"))
    )
    (net (code "76") (name "unconnected-(IO10-3-Pad1)") (class "Default")
      (node (ref "IO10") (pin "1") (pinfunction "3_1") (pintype "passive"))
    )
    (net (code "77") (name "unconnected-(IO11-3-Pad1)") (class "Default")
      (node (ref "IO11") (pin "1") (pinfunction "3_1") (pintype "passive"))
    )
    (net (code "78") (name "unconnected-(IO12-3-Pad1)") (class "Default")
      (node (ref "IO12") (pin "1") (pinfunction "3_1") (pintype "passive"))
    )
    (net (code "79") (name "unconnected-(IO13-3-Pad1)") (class "Default")
      (node (ref "IO13") (pin "1") (pinfunction "3_1") (pintype "passive"))
    )
    (net (code "80") (name "unconnected-(IO14-3-Pad1)") (class "Default")
      (node (ref "IO14") (pin "1") (pinfunction "3_1") (pintype "passive"))
    )
    (net (code "81") (name "unconnected-(IO15-3-Pad1)") (class "Default")
      (node (ref "IO15") (pin "1") (pinfunction "3_1") (pintype "passive"))
    )
    (net (code "82") (name "unconnected-(IO16-3-Pad1)") (class "Default")
      (node (ref "IO16") (pin "1") (pinfunction "3_1") (pintype "passive"))
    )
  )
)
